# CanBus-UP-Schalter-Teil2.net
KiCad netlist of a schematic drawn in EAGLE
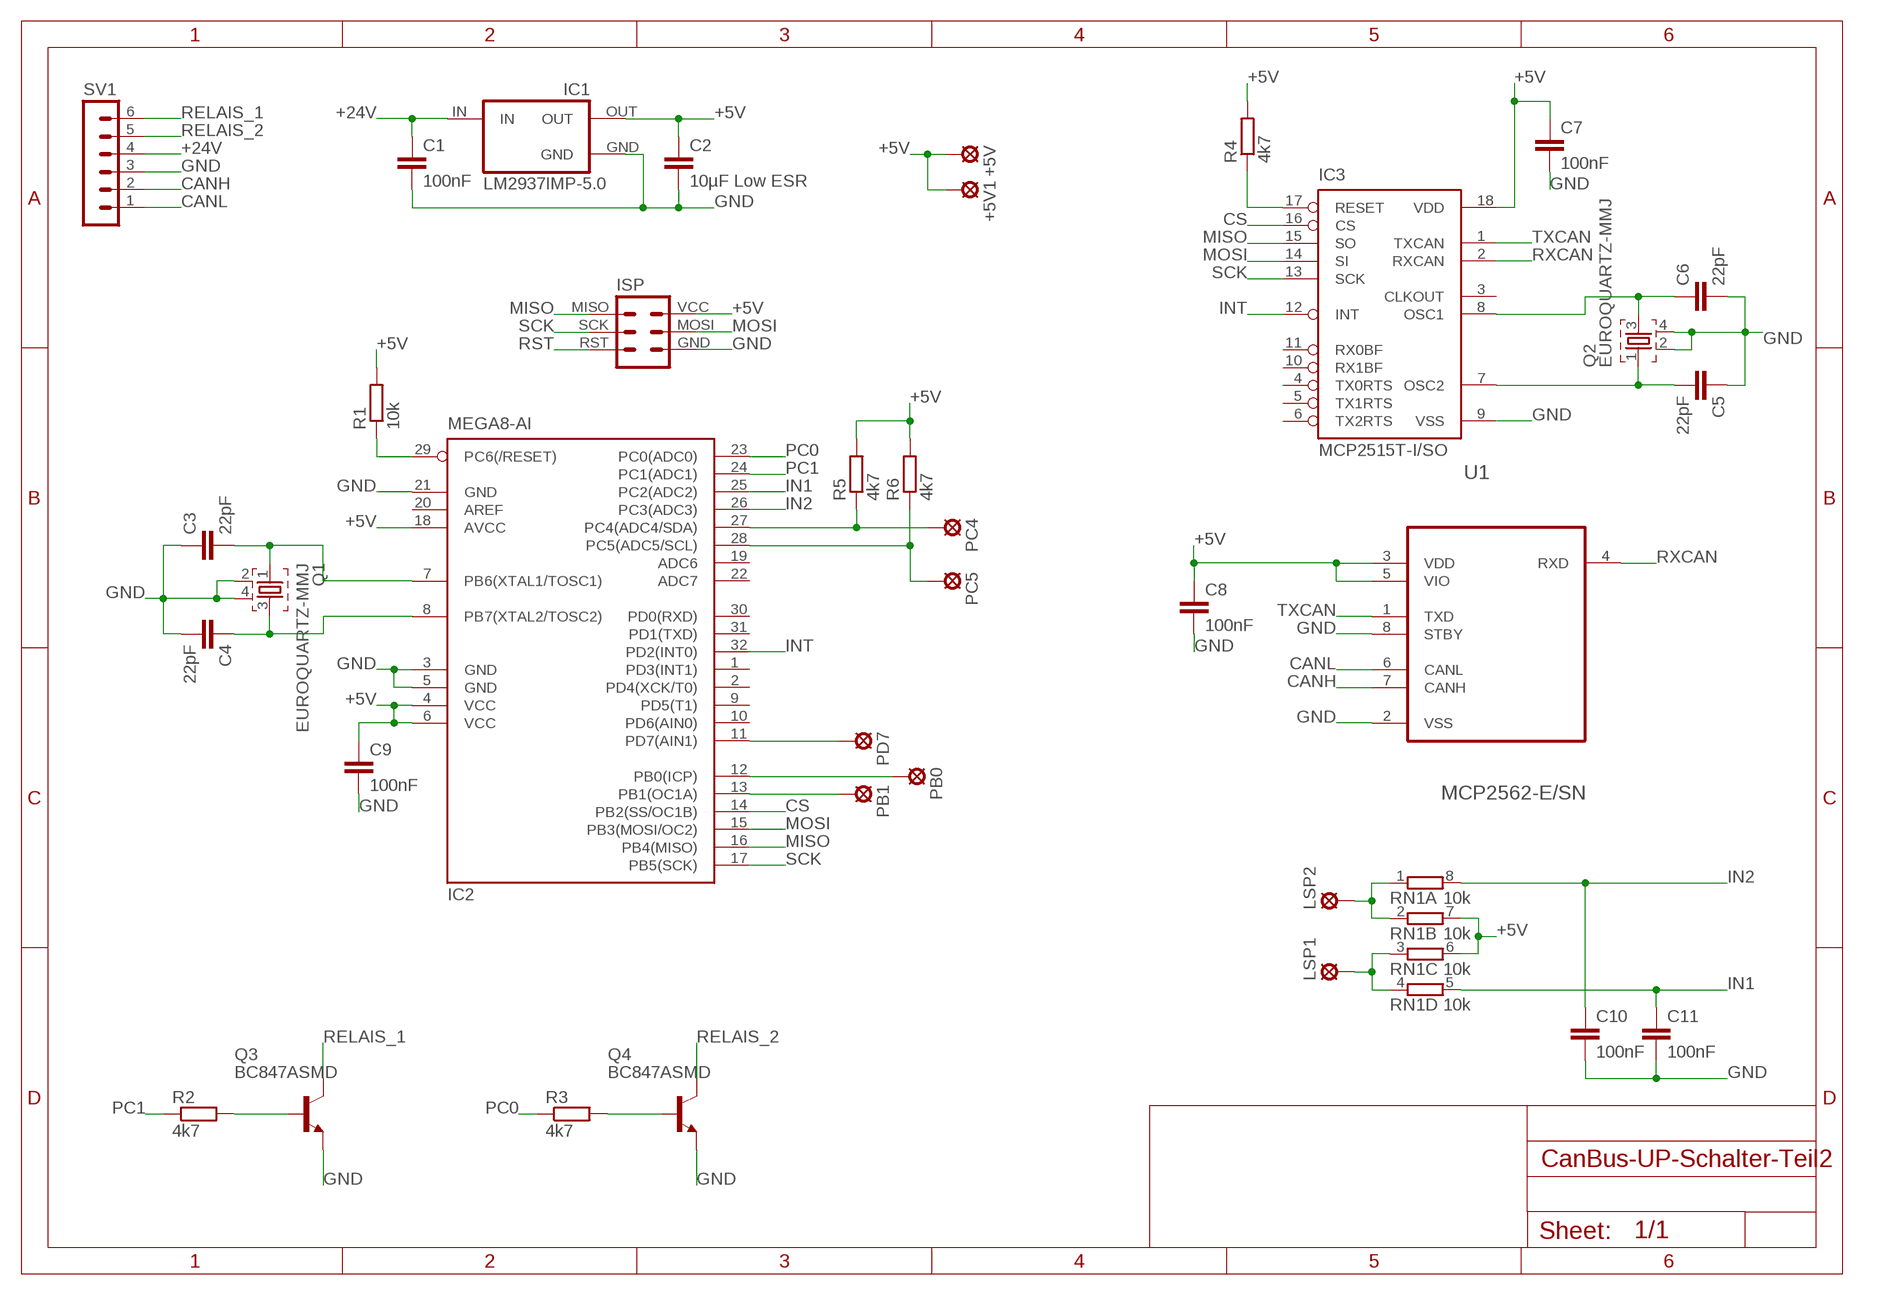
[diagram p0: schematic, sheet 1]

(export (version "E")
  (design (tool "Eeschema 10.0.6"))
  (components
    (comp (ref "+5V")
      (value "LSP13")
      (footprint "eagle-import:LSP13")
      (libsource (lib "eagle-import") (part "LSP13"))
    )
    (comp (ref "+5V1")
      (value "LSP13")
      (footprint "eagle-import:LSP13")
      (libsource (lib "eagle-import") (part "LSP13"))
    )
    (comp (ref "C1")
      (value "100nF")
      (footprint "eagle-import:C0805")
      (libsource (lib "eagle-import") (part "C-EUC0805"))
    )
    (comp (ref "C2")
      (value "10µF Low ESR")
      (footprint "eagle-import:C0805")
      (libsource (lib "eagle-import") (part "C-EUC0805"))
    )
    (comp (ref "C3")
      (value "22pF")
      (footprint "eagle-import:C0805")
      (libsource (lib "eagle-import") (part "C-EUC0805"))
    )
    (comp (ref "C4")
      (value "22pF")
      (footprint "eagle-import:C0805")
      (libsource (lib "eagle-import") (part "C-EUC0805"))
    )
    (comp (ref "C5")
      (value "22pF")
      (footprint "eagle-import:C0805")
      (libsource (lib "eagle-import") (part "C-EUC0805"))
    )
    (comp (ref "C6")
      (value "22pF")
      (footprint "eagle-import:C0805")
      (libsource (lib "eagle-import") (part "C-EUC0805"))
    )
    (comp (ref "C7")
      (value "100nF")
      (footprint "eagle-import:C0805")
      (libsource (lib "eagle-import") (part "C-EUC0805"))
    )
    (comp (ref "C8")
      (value "100nF")
      (footprint "eagle-import:C0805")
      (libsource (lib "eagle-import") (part "C-EUC0805"))
    )
    (comp (ref "C9")
      (value "100nF")
      (footprint "eagle-import:C0805")
      (libsource (lib "eagle-import") (part "C-EUC0805"))
    )
    (comp (ref "C10")
      (value "100nF")
      (footprint "eagle-import:C0805")
      (libsource (lib "eagle-import") (part "C-EUC0805"))
    )
    (comp (ref "C11")
      (value "100nF")
      (footprint "eagle-import:C0805")
      (libsource (lib "eagle-import") (part "C-EUC0805"))
    )
    (comp (ref "IC1")
      (value "LM2937IMP-5.0")
      (footprint "eagle-import:SOT223")
      (libsource (lib "eagle-import") (part "LM2937IMP-5.0"))
    )
    (comp (ref "IC2")
      (value "MEGA8-AI")
      (footprint "eagle-import:TQFP32-08")
      (fields (field (name "MPN") "ATMEGA8-16AU"))
      (libsource (lib "eagle-import") (part "MEGA8-AI"))
    )
    (comp (ref "IC3")
      (value "MCP2515T-I/SO")
      (footprint "eagle-import:SO18L")
      (libsource (lib "eagle-import") (part "MCP2515T-I/SO"))
    )
    (comp (ref "ISP")
      (value "ISPVIAS-ONLY-1.27MM")
      (footprint "eagle-import:ISP-VIAS-ONLY-1.27MM")
      (libsource (lib "eagle-import") (part "ISPVIAS-ONLY-1.27MM"))
    )
    (comp (ref "LSP1")
      (value "LSP13")
      (footprint "eagle-import:LSP13")
      (libsource (lib "eagle-import") (part "LSP13"))
    )
    (comp (ref "LSP2")
      (value "LSP13")
      (footprint "eagle-import:LSP13")
      (libsource (lib "eagle-import") (part "LSP13"))
    )
    (comp (ref "PB0")
      (value "LSP13")
      (footprint "eagle-import:LSP13")
      (libsource (lib "eagle-import") (part "LSP13"))
    )
    (comp (ref "PB1")
      (value "LSP13")
      (footprint "eagle-import:LSP13")
      (libsource (lib "eagle-import") (part "LSP13"))
    )
    (comp (ref "PC4")
      (value "LSP13")
      (footprint "eagle-import:LSP13")
      (libsource (lib "eagle-import") (part "LSP13"))
    )
    (comp (ref "PC5")
      (value "LSP13")
      (footprint "eagle-import:LSP13")
      (libsource (lib "eagle-import") (part "LSP13"))
    )
    (comp (ref "PD7")
      (value "LSP13")
      (footprint "eagle-import:LSP13")
      (libsource (lib "eagle-import") (part "LSP13"))
    )
    (comp (ref "Q1")
      (value "EUROQUARTZ-MMJ")
      (footprint "eagle-import:MJ-5X3.2")
      (libsource (lib "eagle-import") (part "EUROQUARTZ-MMJ"))
    )
    (comp (ref "Q2")
      (value "EUROQUARTZ-MMJ")
      (footprint "eagle-import:MJ-5X3.2")
      (libsource (lib "eagle-import") (part "EUROQUARTZ-MMJ"))
    )
    (comp (ref "Q3")
      (value "BC847ASMD")
      (footprint "eagle-import:SOT23")
      (libsource (lib "eagle-import") (part "BC847SMDA"))
    )
    (comp (ref "Q4")
      (value "BC847ASMD")
      (footprint "eagle-import:SOT23")
      (libsource (lib "eagle-import") (part "BC847SMDA"))
    )
    (comp (ref "R1")
      (value "10k")
      (footprint "eagle-import:R0805")
      (libsource (lib "eagle-import") (part "R-EU_R0805"))
    )
    (comp (ref "R2")
      (value "4k7")
      (footprint "eagle-import:R0805")
      (libsource (lib "eagle-import") (part "R-EU_R0805"))
    )
    (comp (ref "R3")
      (value "4k7")
      (footprint "eagle-import:R0805")
      (libsource (lib "eagle-import") (part "R-EU_R0805"))
    )
    (comp (ref "R4")
      (value "4k7")
      (footprint "eagle-import:R0805")
      (libsource (lib "eagle-import") (part "R-EU_R0805"))
    )
    (comp (ref "R5")
      (value "4k7")
      (footprint "eagle-import:R0805")
      (libsource (lib "eagle-import") (part "R-EU_R0805"))
    )
    (comp (ref "R6")
      (value "4k7")
      (footprint "eagle-import:R0805")
      (libsource (lib "eagle-import") (part "R-EU_R0805"))
    )
    (comp (ref "RN1")
      (value "10k")
      (footprint "eagle-import:0603-ARC")
      (libsource (lib "eagle-import") (part "4R-N0603-ARC"))
    )
    (comp (ref "SV1")
      (value "MA06-1")
      (footprint "eagle-import:MA06-1")
      (libsource (lib "eagle-import") (part "MA06-1"))
    )
    (comp (ref "U1")
      (value "MCP2562-E/SN")
      (footprint "eagle-import:SO08")
      (libsource (lib "eagle-import") (part "MCP2562-E/SN"))
    )
  )
  (nets
    (net (code "1") (name "/+5V") (class "Default")
      (node (ref "+5V") (pin "MP") (pinfunction "MP_MP") (pintype "passive"))
      (node (ref "+5V1") (pin "MP") (pinfunction "MP_MP") (pintype "passive"))
      (node (ref "C2") (pin "1") (pinfunction "1_1") (pintype "passive"))
      (node (ref "C7") (pin "1") (pinfunction "1_1") (pintype "passive"))
      (node (ref "C8") (pin "1") (pinfunction "1_1") (pintype "passive"))
      (node (ref "C9") (pin "1") (pinfunction "1_1") (pintype "passive"))
      (node (ref "IC1") (pin "OUT") (pinfunction "OUT_OUT") (pintype "output"))
      (node (ref "IC2") (pin "18") (pinfunction "AVCC_18") (pintype "power_in"))
      (node (ref "IC2") (pin "4") (pinfunction "VCC_4") (pintype "power_in"))
      (node (ref "IC2") (pin "6") (pinfunction "VCC_6") (pintype "power_in"))
      (node (ref "IC3") (pin "18") (pinfunction "VDD_18") (pintype "power_in"))
      (node (ref "ISP") (pin "VCC") (pinfunction "VCC_VCC") (pintype "passive"))
      (node (ref "R1") (pin "2") (pinfunction "2_2") (pintype "passive"))
      (node (ref "R4") (pin "2") (pinfunction "2_2") (pintype "passive"))
      (node (ref "R5") (pin "2") (pinfunction "2_2") (pintype "passive"))
      (node (ref "R6") (pin "2") (pinfunction "2_2") (pintype "passive"))
      (node (ref "RN1") (pin "6") (pinfunction "2_6") (pintype "passive"))
      (node (ref "RN1") (pin "7") (pinfunction "2_7") (pintype "passive"))
      (node (ref "U1") (pin "3") (pinfunction "VDD_3") (pintype "power_in"))
      (node (ref "U1") (pin "5") (pinfunction "VIO_5") (pintype "power_in"))
    )
    (net (code "2") (name "/+24V") (class "Default")
      (node (ref "C1") (pin "1") (pinfunction "1_1") (pintype "passive"))
      (node (ref "IC1") (pin "IN") (pinfunction "IN_IN") (pintype "input"))
      (node (ref "SV1") (pin "4") (pinfunction "4_4") (pintype "passive"))
    )
    (net (code "3") (name "/CANH") (class "Default")
      (node (ref "SV1") (pin "2") (pinfunction "2_2") (pintype "passive"))
      (node (ref "U1") (pin "7") (pinfunction "CANH_7") (pintype "bidirectional"))
    )
    (net (code "4") (name "/CANL") (class "Default")
      (node (ref "SV1") (pin "1") (pinfunction "1_1") (pintype "passive"))
      (node (ref "U1") (pin "6") (pinfunction "CANL_6") (pintype "bidirectional"))
    )
    (net (code "5") (name "/CS") (class "Default")
      (node (ref "IC2") (pin "14") (pinfunction "PB2(SS/OC1B)_14") (pintype "bidirectional"))
      (node (ref "IC3") (pin "16") (pinfunction "CS_16") (pintype "input"))
    )
    (net (code "6") (name "/GND") (class "Default")
      (node (ref "C1") (pin "2") (pinfunction "2_2") (pintype "passive"))
      (node (ref "C10") (pin "2") (pinfunction "2_2") (pintype "passive"))
      (node (ref "C11") (pin "2") (pinfunction "2_2") (pintype "passive"))
      (node (ref "C2") (pin "2") (pinfunction "2_2") (pintype "passive"))
      (node (ref "C3") (pin "1") (pinfunction "1_1") (pintype "passive"))
      (node (ref "C4") (pin "2") (pinfunction "2_2") (pintype "passive"))
      (node (ref "C5") (pin "1") (pinfunction "1_1") (pintype "passive"))
      (node (ref "C6") (pin "2") (pinfunction "2_2") (pintype "passive"))
      (node (ref "C7") (pin "2") (pinfunction "2_2") (pintype "passive"))
      (node (ref "C8") (pin "2") (pinfunction "2_2") (pintype "passive"))
      (node (ref "C9") (pin "2") (pinfunction "2_2") (pintype "passive"))
      (node (ref "IC1") (pin "GND") (pinfunction "GND_GND") (pintype "power_in"))
      (node (ref "IC2") (pin "21") (pinfunction "GND_21") (pintype "power_in"))
      (node (ref "IC2") (pin "3") (pinfunction "GND_3") (pintype "power_in"))
      (node (ref "IC2") (pin "5") (pinfunction "GND_5") (pintype "power_in"))
      (node (ref "IC3") (pin "9") (pinfunction "VSS_9") (pintype "power_in"))
      (node (ref "ISP") (pin "GND") (pinfunction "GND_GND") (pintype "passive"))
      (node (ref "Q1") (pin "2") (pinfunction "2_2") (pintype "passive"))
      (node (ref "Q1") (pin "4") (pinfunction "4_4") (pintype "passive"))
      (node (ref "Q2") (pin "2") (pinfunction "2_2") (pintype "passive"))
      (node (ref "Q2") (pin "4") (pinfunction "4_4") (pintype "passive"))
      (node (ref "Q3") (pin "2") (pinfunction "E_2") (pintype "passive"))
      (node (ref "Q4") (pin "2") (pinfunction "E_2") (pintype "passive"))
      (node (ref "SV1") (pin "3") (pinfunction "3_3") (pintype "passive"))
      (node (ref "U1") (pin "2") (pinfunction "VSS_2") (pintype "power_in"))
      (node (ref "U1") (pin "8") (pinfunction "STBY_8") (pintype "input"))
    )
    (net (code "7") (name "/IN1") (class "Default")
      (node (ref "C11") (pin "1") (pinfunction "1_1") (pintype "passive"))
      (node (ref "IC2") (pin "25") (pinfunction "PC2(ADC2)_25") (pintype "bidirectional"))
      (node (ref "RN1") (pin "5") (pinfunction "2_5") (pintype "passive"))
    )
    (net (code "8") (name "/IN2") (class "Default")
      (node (ref "C10") (pin "1") (pinfunction "1_1") (pintype "passive"))
      (node (ref "IC2") (pin "26") (pinfunction "PC3(ADC3)_26") (pintype "bidirectional"))
      (node (ref "RN1") (pin "8") (pinfunction "2_8") (pintype "passive"))
    )
    (net (code "9") (name "/INT") (class "Default")
      (node (ref "IC2") (pin "32") (pinfunction "PD2(INT0)_32") (pintype "bidirectional"))
      (node (ref "IC3") (pin "12") (pinfunction "INT_12") (pintype "output"))
    )
    (net (code "10") (name "/MISO") (class "Default")
      (node (ref "IC2") (pin "16") (pinfunction "PB4(MISO)_16") (pintype "bidirectional"))
      (node (ref "IC3") (pin "15") (pinfunction "SO_15") (pintype "output"))
      (node (ref "ISP") (pin "MISO") (pinfunction "MISO_MISO") (pintype "passive"))
    )
    (net (code "11") (name "/MOSI") (class "Default")
      (node (ref "IC2") (pin "15") (pinfunction "PB3(MOSI/OC2)_15") (pintype "bidirectional"))
      (node (ref "IC3") (pin "14") (pinfunction "SI_14") (pintype "input"))
      (node (ref "ISP") (pin "MOSI") (pinfunction "MOSI_MOSI") (pintype "passive"))
    )
    (net (code "12") (name "/PC0") (class "Default")
      (node (ref "IC2") (pin "23") (pinfunction "PC0(ADC0)_23") (pintype "bidirectional"))
      (node (ref "R3") (pin "1") (pinfunction "1_1") (pintype "passive"))
    )
    (net (code "13") (name "/PC1") (class "Default")
      (node (ref "IC2") (pin "24") (pinfunction "PC1(ADC1)_24") (pintype "bidirectional"))
      (node (ref "R2") (pin "1") (pinfunction "1_1") (pintype "passive"))
    )
    (net (code "14") (name "/RELAIS_1") (class "Default")
      (node (ref "Q3") (pin "3") (pinfunction "C_3") (pintype "passive"))
      (node (ref "SV1") (pin "6") (pinfunction "6_6") (pintype "passive"))
    )
    (net (code "15") (name "/RELAIS_2") (class "Default")
      (node (ref "Q4") (pin "3") (pinfunction "C_3") (pintype "passive"))
      (node (ref "SV1") (pin "5") (pinfunction "5_5") (pintype "passive"))
    )
    (net (code "16") (name "/RST") (class "Default")
      (node (ref "IC2") (pin "29") (pinfunction "PC6(/RESET)_29") (pintype "bidirectional"))
      (node (ref "ISP") (pin "RST") (pinfunction "RST_RST") (pintype "passive"))
      (node (ref "R1") (pin "1") (pinfunction "1_1") (pintype "passive"))
    )
    (net (code "17") (name "/RXCAN") (class "Default")
      (node (ref "IC3") (pin "2") (pinfunction "RXCAN_2") (pintype "input"))
      (node (ref "U1") (pin "4") (pinfunction "RXD_4") (pintype "output"))
    )
    (net (code "18") (name "/SCK") (class "Default")
      (node (ref "IC2") (pin "17") (pinfunction "PB5(SCK)_17") (pintype "bidirectional"))
      (node (ref "IC3") (pin "13") (pinfunction "SCK_13") (pintype "input"))
      (node (ref "ISP") (pin "SCK") (pinfunction "SCK_SCK") (pintype "passive"))
    )
    (net (code "19") (name "/TXCAN") (class "Default")
      (node (ref "IC3") (pin "1") (pinfunction "TXCAN_1") (pintype "output"))
      (node (ref "U1") (pin "1") (pinfunction "TXD_1") (pintype "input"))
    )
    (net (code "20") (name "Net-(IC2-PB0(ICP))") (class "Default")
      (node (ref "IC2") (pin "12") (pinfunction "PB0(ICP)_12") (pintype "bidirectional"))
      (node (ref "PB0") (pin "MP") (pinfunction "MP_MP") (pintype "passive"))
    )
    (net (code "21") (name "Net-(IC2-PB1(OC1A))") (class "Default")
      (node (ref "IC2") (pin "13") (pinfunction "PB1(OC1A)_13") (pintype "bidirectional"))
      (node (ref "PB1") (pin "MP") (pinfunction "MP_MP") (pintype "passive"))
    )
    (net (code "22") (name "Net-(IC2-PB6(XTAL1{slash}TOSC1))") (class "Default")
      (node (ref "C3") (pin "2") (pinfunction "2_2") (pintype "passive"))
      (node (ref "IC2") (pin "7") (pinfunction "PB6(XTAL1/TOSC1)_7") (pintype "bidirectional"))
      (node (ref "Q1") (pin "1") (pinfunction "1_1") (pintype "passive"))
    )
    (net (code "23") (name "Net-(IC2-PB7(XTAL2{slash}TOSC2))") (class "Default")
      (node (ref "C4") (pin "1") (pinfunction "1_1") (pintype "passive"))
      (node (ref "IC2") (pin "8") (pinfunction "PB7(XTAL2/TOSC2)_8") (pintype "bidirectional"))
      (node (ref "Q1") (pin "3") (pinfunction "3_3") (pintype "passive"))
    )
    (net (code "24") (name "Net-(IC2-PC4(ADC4{slash}SDA))") (class "Default")
      (node (ref "IC2") (pin "27") (pinfunction "PC4(ADC4/SDA)_27") (pintype "bidirectional"))
      (node (ref "PC4") (pin "MP") (pinfunction "MP_MP") (pintype "passive"))
      (node (ref "R5") (pin "1") (pinfunction "1_1") (pintype "passive"))
    )
    (net (code "25") (name "Net-(IC2-PC5(ADC5{slash}SCL))") (class "Default")
      (node (ref "IC2") (pin "28") (pinfunction "PC5(ADC5/SCL)_28") (pintype "bidirectional"))
      (node (ref "PC5") (pin "MP") (pinfunction "MP_MP") (pintype "passive"))
      (node (ref "R6") (pin "1") (pinfunction "1_1") (pintype "passive"))
    )
    (net (code "26") (name "Net-(IC2-PD7(AIN1))") (class "Default")
      (node (ref "IC2") (pin "11") (pinfunction "PD7(AIN1)_11") (pintype "bidirectional"))
      (node (ref "PD7") (pin "MP") (pinfunction "MP_MP") (pintype "passive"))
    )
    (net (code "27") (name "Net-(IC3-OSC1)") (class "Default")
      (node (ref "C6") (pin "1") (pinfunction "1_1") (pintype "passive"))
      (node (ref "IC3") (pin "8") (pinfunction "OSC1_8") (pintype "input"))
      (node (ref "Q2") (pin "3") (pinfunction "3_3") (pintype "passive"))
    )
    (net (code "28") (name "Net-(IC3-OSC2)") (class "Default")
      (node (ref "C5") (pin "2") (pinfunction "2_2") (pintype "passive"))
      (node (ref "IC3") (pin "7") (pinfunction "OSC2_7") (pintype "output"))
      (node (ref "Q2") (pin "1") (pinfunction "1_1") (pintype "passive"))
    )
    (net (code "29") (name "Net-(IC3-RESET)") (class "Default")
      (node (ref "IC3") (pin "17") (pinfunction "RESET_17") (pintype "input"))
      (node (ref "R4") (pin "1") (pinfunction "1_1") (pintype "passive"))
    )
    (net (code "30") (name "Net-(Q3-B)") (class "Default")
      (node (ref "Q3") (pin "1") (pinfunction "B_1") (pintype "passive"))
      (node (ref "R2") (pin "2") (pinfunction "2_2") (pintype "passive"))
    )
    (net (code "31") (name "Net-(Q4-B)") (class "Default")
      (node (ref "Q4") (pin "1") (pinfunction "B_1") (pintype "passive"))
      (node (ref "R3") (pin "2") (pinfunction "2_2") (pintype "passive"))
    )
    (net (code "32") (name "Net-(RN1B-1)") (class "Default")
      (node (ref "LSP2") (pin "MP") (pinfunction "MP_MP") (pintype "passive"))
      (node (ref "RN1") (pin "1") (pinfunction "1_1") (pintype "passive"))
      (node (ref "RN1") (pin "2") (pinfunction "1_2") (pintype "passive"))
    )
    (net (code "33") (name "Net-(RN1C-1)") (class "Default")
      (node (ref "LSP1") (pin "MP") (pinfunction "MP_MP") (pintype "passive"))
      (node (ref "RN1") (pin "3") (pinfunction "1_3") (pintype "passive"))
      (node (ref "RN1") (pin "4") (pinfunction "1_4") (pintype "passive"))
    )
    (net (code "34") (name "unconnected-(IC2-ADC6-Pad19)") (class "Default")
      (node (ref "IC2") (pin "19") (pinfunction "ADC6_19") (pintype "bidirectional"))
    )
    (net (code "35") (name "unconnected-(IC2-ADC7-Pad22)") (class "Default")
      (node (ref "IC2") (pin "22") (pinfunction "ADC7_22") (pintype "bidirectional"))
    )
    (net (code "36") (name "unconnected-(IC2-AREF-Pad20)") (class "Default")
      (node (ref "IC2") (pin "20") (pinfunction "AREF_20") (pintype "passive"))
    )
    (net (code "37") (name "unconnected-(IC2-PD0(RXD)-Pad30)") (class "Default")
      (node (ref "IC2") (pin "30") (pinfunction "PD0(RXD)_30") (pintype "bidirectional"))
    )
    (net (code "38") (name "unconnected-(IC2-PD1(TXD)-Pad31)") (class "Default")
      (node (ref "IC2") (pin "31") (pinfunction "PD1(TXD)_31") (pintype "bidirectional"))
    )
    (net (code "39") (name "unconnected-(IC2-PD3(INT1)-Pad1)") (class "Default")
      (node (ref "IC2") (pin "1") (pinfunction "PD3(INT1)_1") (pintype "bidirectional"))
    )
    (net (code "40") (name "unconnected-(IC2-PD4(XCK{slash}T0)-Pad2)") (class "Default")
      (node (ref "IC2") (pin "2") (pinfunction "PD4(XCK/T0)_2") (pintype "bidirectional"))
    )
    (net (code "41") (name "unconnected-(IC2-PD5(T1)-Pad9)") (class "Default")
      (node (ref "IC2") (pin "9") (pinfunction "PD5(T1)_9") (pintype "bidirectional"))
    )
    (net (code "42") (name "unconnected-(IC2-PD6(AIN0)-Pad10)") (class "Default")
      (node (ref "IC2") (pin "10") (pinfunction "PD6(AIN0)_10") (pintype "bidirectional"))
    )
    (net (code "43") (name "unconnected-(IC3-CLKOUT-Pad3)") (class "Default")
      (node (ref "IC3") (pin "3") (pinfunction "CLKOUT_3") (pintype "output"))
    )
    (net (code "44") (name "unconnected-(IC3-RX0BF-Pad11)") (class "Default")
      (node (ref "IC3") (pin "11") (pinfunction "RX0BF_11") (pintype "output"))
    )
    (net (code "45") (name "unconnected-(IC3-RX1BF-Pad10)") (class "Default")
      (node (ref "IC3") (pin "10") (pinfunction "RX1BF_10") (pintype "output"))
    )
    (net (code "46") (name "unconnected-(IC3-TX0RTS-Pad4)") (class "Default")
      (node (ref "IC3") (pin "4") (pinfunction "TX0RTS_4") (pintype "input"))
    )
    (net (code "47") (name "unconnected-(IC3-TX1RTS-Pad5)") (class "Default")
      (node (ref "IC3") (pin "5") (pinfunction "TX1RTS_5") (pintype "input"))
    )
    (net (code "48") (name "unconnected-(IC3-TX2RTS-Pad6)") (class "Default")
      (node (ref "IC3") (pin "6") (pinfunction "TX2RTS_6") (pintype "input"))
    )
  )
)
